# 24_LMS2_RX2_BB_ADC.net
KiCad netlist of a schematic drawn in Altium Designer
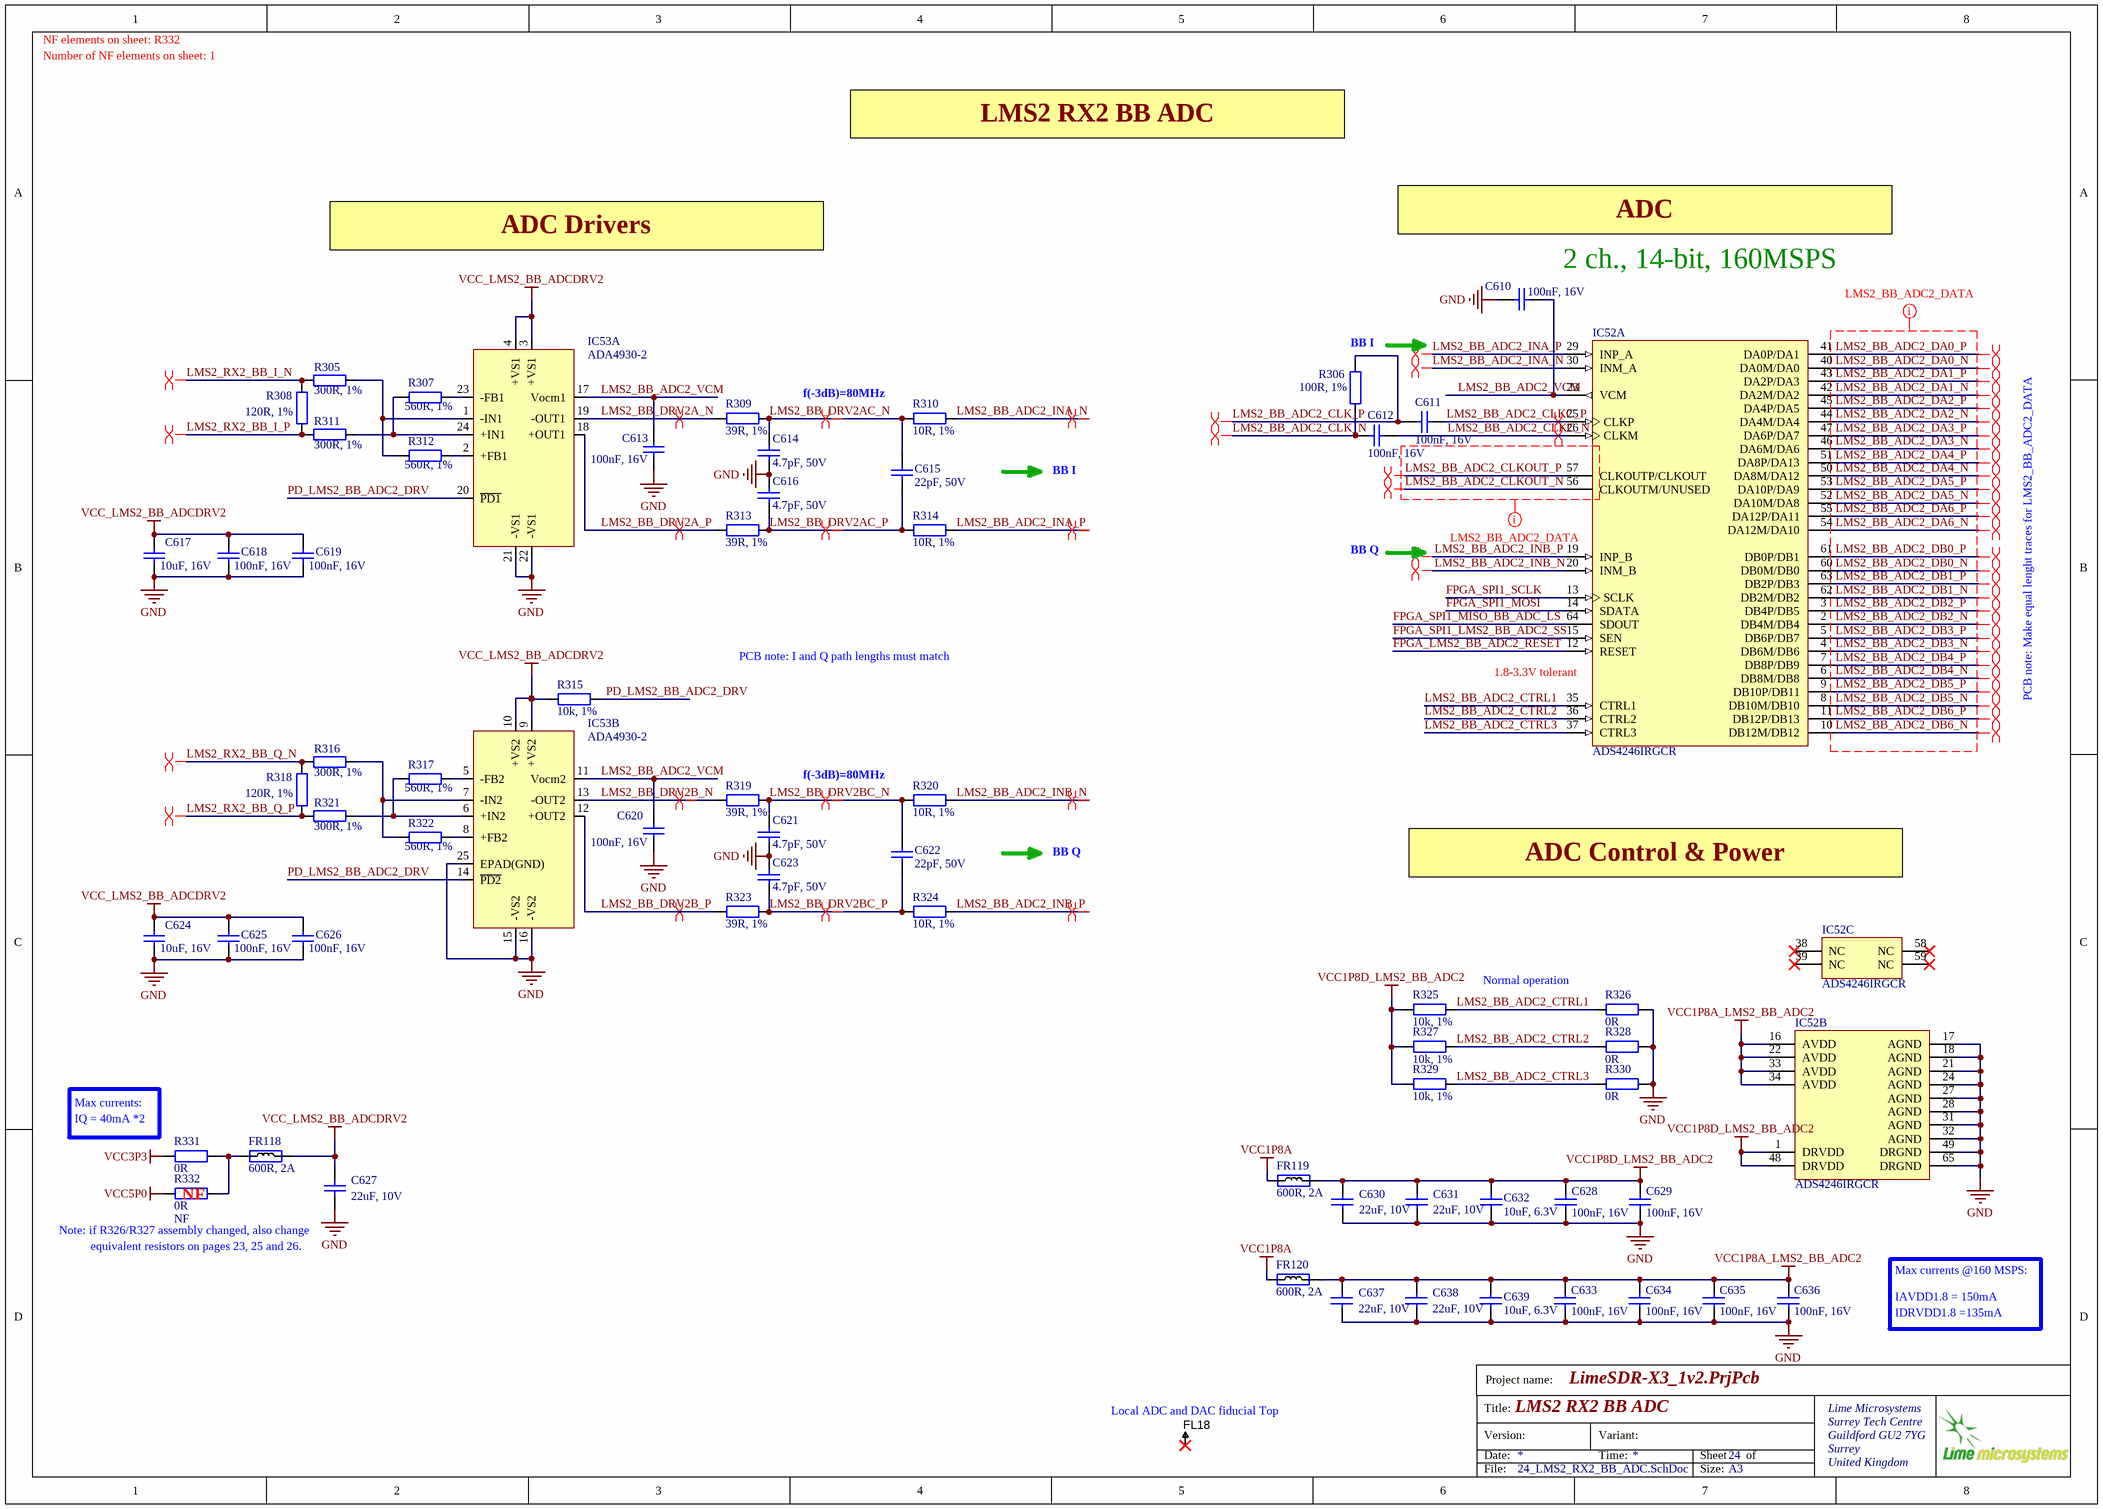
[diagram p0: 24_LMS2_RX2_BB_ADC.SchDoc]

(export (version "E")
  (design (tool "Eeschema 10.0.6"))
  (components
    (comp (ref "C610")
      (value "100nF, 16V")
      (footprint "CAP0402")
      (fields (field (name "TOLERANCE") "10 %") (field (name "MANUFACTURER") "Murata Electronics"))
      (libsource (lib "") (part "Cap_0603_6"))
    )
    (comp (ref "C611")
      (value "100nF, 16V")
      (footprint "CAP0402")
      (fields (field (name "TOLERANCE") "10 %") (field (name "MANUFACTURER") "Murata Electronics"))
      (libsource (lib "") (part "Cap_0603_6"))
    )
    (comp (ref "C612")
      (value "100nF, 16V")
      (footprint "CAP0402")
      (fields (field (name "TOLERANCE") "10 %") (field (name "MANUFACTURER") "Murata Electronics"))
      (libsource (lib "LimeFPGAboard_schLib") (part "Cap_0603"))
    )
    (comp (ref "C613")
      (value "100nF, 16V")
      (footprint "CAP0402")
      (fields (field (name "TOLERANCE") "10 %") (field (name "MANUFACTURER") "Murata Electronics"))
      (libsource (lib "LimeFPGAboard_schLib") (part "Cap_0603"))
    )
    (comp (ref "C614")
      (value "4.7pF, 50V")
      (footprint "CAP0402")
      (fields (field (name "MANUFACTURER") "MURATA"))
      (libsource (lib "") (part "Cap_0402_1"))
    )
    (comp (ref "C615")
      (value "22pF, 50V")
      (footprint "CAP0402")
      (fields (field (name "TOLERANCE") "±5%") (field (name "MANUFACTURER") "Yageo"))
      (libsource (lib "LimeMicroAltiumLib_schLib") (part "Cap_0402"))
    )
    (comp (ref "C616")
      (value "4.7pF, 50V")
      (footprint "CAP0402")
      (fields (field (name "MANUFACTURER") "MURATA"))
      (libsource (lib "") (part "Cap_0402_1"))
    )
    (comp (ref "C617")
      (value "10uF, 16V")
      (footprint "CAP0603")
      (fields (field (name "MANUFACTURER") "Yageo") (field (name "TOLERANCE") "±20%"))
      (libsource (lib "LimeMicroAltiumLib_schLib") (part "Cap_0603"))
    )
    (comp (ref "C618")
      (value "100nF, 16V")
      (footprint "CAP0402")
      (fields (field (name "TOLERANCE") "10 %") (field (name "MANUFACTURER") "Murata Electronics"))
      (libsource (lib "LimeFPGAboard_schLib") (part "Cap_0603"))
    )
    (comp (ref "C619")
      (value "100nF, 16V")
      (footprint "CAP0402")
      (fields (field (name "TOLERANCE") "10 %") (field (name "MANUFACTURER") "Murata Electronics"))
      (libsource (lib "LimeFPGAboard_schLib") (part "Cap_0603"))
    )
    (comp (ref "C620")
      (value "100nF, 16V")
      (footprint "CAP0402")
      (fields (field (name "TOLERANCE") "10 %") (field (name "MANUFACTURER") "Murata Electronics"))
      (libsource (lib "") (part "Cap_0603_5"))
    )
    (comp (ref "C621")
      (value "4.7pF, 50V")
      (footprint "CAP0402")
      (fields (field (name "MANUFACTURER") "MURATA"))
      (libsource (lib "") (part "Cap_0402_1"))
    )
    (comp (ref "C622")
      (value "22pF, 50V")
      (footprint "CAP0402")
      (fields (field (name "TOLERANCE") "±5%") (field (name "MANUFACTURER") "Yageo"))
      (libsource (lib "LimeMicroAltiumLib_schLib") (part "Cap_0402"))
    )
    (comp (ref "C623")
      (value "4.7pF, 50V")
      (footprint "CAP0402")
      (fields (field (name "MANUFACTURER") "MURATA"))
      (libsource (lib "") (part "Cap_0402_1"))
    )
    (comp (ref "C624")
      (value "10uF, 16V")
      (footprint "CAP0603")
      (fields (field (name "MANUFACTURER") "Yageo") (field (name "TOLERANCE") "±20%"))
      (libsource (lib "LimeMicroAltiumLib_schLib") (part "Cap_0603"))
    )
    (comp (ref "C625")
      (value "100nF, 16V")
      (footprint "CAP0402")
      (fields (field (name "TOLERANCE") "10 %") (field (name "MANUFACTURER") "Murata Electronics"))
      (libsource (lib "LimeFPGAboard_schLib") (part "Cap_0603"))
    )
    (comp (ref "C626")
      (value "100nF, 16V")
      (footprint "CAP0402")
      (fields (field (name "TOLERANCE") "10 %") (field (name "MANUFACTURER") "Murata Electronics"))
      (libsource (lib "LimeFPGAboard_schLib") (part "Cap_0603"))
    )
    (comp (ref "C627")
      (value "22uF, 10V")
      (footprint "CAP0603")
      (fields (field (name "TOLERANCE") "20 %") (field (name "MANUFACTURER") "TDK Corporation"))
      (libsource (lib "") (part "Cap_0603_7"))
    )
    (comp (ref "C628")
      (value "100nF, 16V")
      (footprint "CAP0402")
      (fields (field (name "TOLERANCE") "10 %") (field (name "MANUFACTURER") "Murata Electronics"))
      (libsource (lib "") (part "Cap_0603_3"))
    )
    (comp (ref "C629")
      (value "100nF, 16V")
      (footprint "CAP0402")
      (fields (field (name "TOLERANCE") "10 %") (field (name "MANUFACTURER") "Murata Electronics"))
      (libsource (lib "") (part "Cap_0603_3"))
    )
    (comp (ref "C630")
      (value "22uF, 10V")
      (footprint "CAP0603")
      (fields (field (name "TOLERANCE") "20 %") (field (name "MANUFACTURER") "TDK Corporation"))
      (libsource (lib "") (part "Cap_0603_3"))
    )
    (comp (ref "C631")
      (value "22uF, 10V")
      (footprint "CAP0603")
      (fields (field (name "TOLERANCE") "20 %") (field (name "MANUFACTURER") "TDK Corporation"))
      (libsource (lib "") (part "Cap_0603_3"))
    )
    (comp (ref "C632")
      (value "10uF, 6.3V")
      (footprint "CAP0603")
      (fields (field (name "TOLERANCE") "±20%") (field (name "MANUFACTURER") "Yageo"))
      (libsource (lib "") (part "Cap_0603_1"))
    )
    (comp (ref "C633")
      (value "100nF, 16V")
      (footprint "CAP0402")
      (fields (field (name "TOLERANCE") "10 %") (field (name "MANUFACTURER") "Murata Electronics"))
      (libsource (lib "") (part "Cap_0603_4"))
    )
    (comp (ref "C634")
      (value "100nF, 16V")
      (footprint "CAP0402")
      (fields (field (name "TOLERANCE") "10 %") (field (name "MANUFACTURER") "Murata Electronics"))
      (libsource (lib "") (part "Cap_0603_4"))
    )
    (comp (ref "C635")
      (value "100nF, 16V")
      (footprint "CAP0402")
      (fields (field (name "TOLERANCE") "10 %") (field (name "MANUFACTURER") "Murata Electronics"))
      (libsource (lib "") (part "Cap_0603_4"))
    )
    (comp (ref "C636")
      (value "100nF, 16V")
      (footprint "CAP0402")
      (fields (field (name "TOLERANCE") "10 %") (field (name "MANUFACTURER") "Murata Electronics"))
      (libsource (lib "") (part "Cap_0603_4"))
    )
    (comp (ref "C637")
      (value "22uF, 10V")
      (footprint "CAP0603")
      (fields (field (name "TOLERANCE") "20 %") (field (name "MANUFACTURER") "TDK Corporation"))
      (libsource (lib "") (part "Cap_0603_4"))
    )
    (comp (ref "C638")
      (value "22uF, 10V")
      (footprint "CAP0603")
      (fields (field (name "TOLERANCE") "20 %") (field (name "MANUFACTURER") "TDK Corporation"))
      (libsource (lib "") (part "Cap_0603_4"))
    )
    (comp (ref "C639")
      (value "10uF, 6.3V")
      (footprint "CAP0603")
      (fields (field (name "TOLERANCE") "±20%") (field (name "MANUFACTURER") "Yageo"))
      (libsource (lib "") (part "Cap_0603_2"))
    )
    (comp (ref "FL18")
      (value "Fiducial")
      (footprint "Fiducial_local")
      (libsource (lib "LimeMicroAltiumLib_schLib") (part "Fiducial"))
    )
    (comp (ref "FR118")
      (value "600R, 2A")
      (footprint "RES0805")
      (fields (field (name "MANUFACTURER") "TDK Corporation"))
      (libsource (lib "LimeMicroAltiumLib_schLib") (part "Ferrite"))
    )
    (comp (ref "FR119")
      (value "600R, 2A")
      (footprint "RES0805")
      (fields (field (name "MANUFACTURER") "TDK Corporation"))
      (libsource (lib "LimeFPGAboard_schLib") (part "Ferrite"))
    )
    (comp (ref "FR120")
      (value "600R, 2A")
      (footprint "RES0805")
      (fields (field (name "MANUFACTURER") "TDK Corporation"))
      (libsource (lib "LimeFPGAboard_schLib") (part "Ferrite"))
    )
    (comp (ref "IC52")
      (value "ADS4246IRGCR")
      (footprint "TI-RGC64-7400X7400TP_V")
      (description "14-Bit 160 MSPS Dual Low Power ADC, -40 to 85 degC, 64-pin QFN (RGC64), Green (RoHS & no Sb/Br)")
      (fields (field (name "MANUFACTURER") "Texas Instruments"))
      (libsource (lib "") (part "ADS4246IRGCR_1"))
    )
    (comp (ref "IC53")
      (value "ADA4930-2")
      (footprint "ADA4930-2_LFCSP-24")
      (fields (field (name "MANUFACTURER") "Analog Devices Inc."))
      (libsource (lib "LimeMicroAltiumLib_schLib") (part "ADA4930-2"))
    )
    (comp (ref "R305")
      (value "300R, 1%")
      (footprint "RES0402")
      (fields (field (name "TOLERANCE") "±1%") (field (name "MANUFACTURER") "Vishay Dale"))
      (libsource (lib "LimeFPGAboard_schLib") (part "Res_0402"))
    )
    (comp (ref "R306")
      (value "100R, 1%")
      (footprint "RES0402")
      (fields (field (name "TOLERANCE") "±1%") (field (name "MANUFACTURER") "Stackpole Electronics Inc."))
      (libsource (lib "LimeFPGAboard_schLib") (part "Res_0402"))
    )
    (comp (ref "R307")
      (value "560R, 1%")
      (footprint "RES0402")
      (fields (field (name "TOLERANCE") "±1%") (field (name "MANUFACTURER") "Vishay Dale"))
      (libsource (lib "LimeFPGAboard_schLib") (part "Res_0402"))
    )
    (comp (ref "R308")
      (value "120R, 1%")
      (footprint "RES0402")
      (fields (field (name "MANUFACTURER") "Yageo") (field (name "TOLERANCE") "1%"))
      (libsource (lib "") (part "Res_0402_1"))
    )
    (comp (ref "R309")
      (value "39R, 1%")
      (footprint "RES0402")
      (fields (field (name "MANUFACTURER") "Yageo") (field (name "TOLERANCE") "1%"))
      (libsource (lib "LimeMicroAltiumLib_schLib") (part "Res_0402"))
    )
    (comp (ref "R310")
      (value "10R, 1%")
      (footprint "RES0402")
      (fields (field (name "TOLERANCE") "1%"))
      (libsource (lib "LimeMicroAltiumLib_schLib") (part "Res_0402"))
    )
    (comp (ref "R311")
      (value "300R, 1%")
      (footprint "RES0402")
      (fields (field (name "TOLERANCE") "±1%") (field (name "MANUFACTURER") "Vishay Dale"))
      (libsource (lib "LimeFPGAboard_schLib") (part "Res_0402"))
    )
    (comp (ref "R312")
      (value "560R, 1%")
      (footprint "RES0402")
      (fields (field (name "TOLERANCE") "±1%") (field (name "MANUFACTURER") "Vishay Dale"))
      (libsource (lib "LimeFPGAboard_schLib") (part "Res_0402"))
    )
    (comp (ref "R313")
      (value "39R, 1%")
      (footprint "RES0402")
      (fields (field (name "MANUFACTURER") "Yageo") (field (name "TOLERANCE") "1%"))
      (libsource (lib "LimeMicroAltiumLib_schLib") (part "Res_0402"))
    )
    (comp (ref "R314")
      (value "10R, 1%")
      (footprint "RES0402")
      (fields (field (name "TOLERANCE") "1%"))
      (libsource (lib "LimeMicroAltiumLib_schLib") (part "Res_0402"))
    )
    (comp (ref "R315")
      (value "10k, 1%")
      (footprint "RES0402")
      (fields (field (name "MANUFACTURER") "Yageo") (field (name "TOLERANCE") "±1%"))
      (libsource (lib "LimeMicroAltiumLib_schLib") (part "Res_0402"))
    )
    (comp (ref "R316")
      (value "300R, 1%")
      (footprint "RES0402")
      (fields (field (name "TOLERANCE") "±1%") (field (name "MANUFACTURER") "Vishay Dale"))
      (libsource (lib "LimeFPGAboard_schLib") (part "Res_0402"))
    )
    (comp (ref "R317")
      (value "560R, 1%")
      (footprint "RES0402")
      (fields (field (name "TOLERANCE") "±1%") (field (name "MANUFACTURER") "Vishay Dale"))
      (libsource (lib "LimeFPGAboard_schLib") (part "Res_0402"))
    )
    (comp (ref "R318")
      (value "120R, 1%")
      (footprint "RES0402")
      (fields (field (name "MANUFACTURER") "Yageo") (field (name "TOLERANCE") "1%"))
      (libsource (lib "") (part "Res_0402_1"))
    )
    (comp (ref "R319")
      (value "39R, 1%")
      (footprint "RES0402")
      (fields (field (name "MANUFACTURER") "Yageo") (field (name "TOLERANCE") "1%"))
      (libsource (lib "LimeMicroAltiumLib_schLib") (part "Res_0402"))
    )
    (comp (ref "R320")
      (value "10R, 1%")
      (footprint "RES0402")
      (fields (field (name "TOLERANCE") "1%"))
      (libsource (lib "LimeMicroAltiumLib_schLib") (part "Res_0402"))
    )
    (comp (ref "R321")
      (value "300R, 1%")
      (footprint "RES0402")
      (fields (field (name "TOLERANCE") "±1%") (field (name "MANUFACTURER") "Vishay Dale"))
      (libsource (lib "LimeFPGAboard_schLib") (part "Res_0402"))
    )
    (comp (ref "R322")
      (value "560R, 1%")
      (footprint "RES0402")
      (fields (field (name "TOLERANCE") "±1%") (field (name "MANUFACTURER") "Vishay Dale"))
      (libsource (lib "LimeFPGAboard_schLib") (part "Res_0402"))
    )
    (comp (ref "R323")
      (value "39R, 1%")
      (footprint "RES0402")
      (fields (field (name "MANUFACTURER") "Yageo") (field (name "TOLERANCE") "1%"))
      (libsource (lib "LimeMicroAltiumLib_schLib") (part "Res_0402"))
    )
    (comp (ref "R324")
      (value "10R, 1%")
      (footprint "RES0402")
      (fields (field (name "TOLERANCE") "1%"))
      (libsource (lib "LimeMicroAltiumLib_schLib") (part "Res_0402"))
    )
    (comp (ref "R325")
      (value "10k, 1%")
      (footprint "RES0402")
      (fields (field (name "MANUFACTURER") "Yageo") (field (name "TOLERANCE") "±1%"))
      (libsource (lib "LimeMicroAltiumLib_schLib") (part "Res_0402"))
    )
    (comp (ref "R326")
      (value "0R")
      (footprint "RES0402")
      (fields (field (name "MANUFACTURER") "Yageo"))
      (libsource (lib "LimeFPGAboard_schLib") (part "Res_0402"))
    )
    (comp (ref "R327")
      (value "10k, 1%")
      (footprint "RES0402")
      (fields (field (name "MANUFACTURER") "Yageo") (field (name "TOLERANCE") "±1%"))
      (libsource (lib "LimeMicroAltiumLib_schLib") (part "Res_0402"))
    )
    (comp (ref "R328")
      (value "0R")
      (footprint "RES0402")
      (fields (field (name "MANUFACTURER") "Yageo"))
      (libsource (lib "LimeFPGAboard_schLib") (part "Res_0402"))
    )
    (comp (ref "R329")
      (value "10k, 1%")
      (footprint "RES0402")
      (fields (field (name "MANUFACTURER") "Yageo") (field (name "TOLERANCE") "±1%"))
      (libsource (lib "LimeMicroAltiumLib_schLib") (part "Res_0402"))
    )
    (comp (ref "R330")
      (value "0R")
      (footprint "RES0402")
      (fields (field (name "MANUFACTURER") "Yageo"))
      (libsource (lib "LimeFPGAboard_schLib") (part "Res_0402"))
    )
    (comp (ref "R331")
      (value "0R")
      (footprint "RES0402")
      (fields (field (name "MANUFACTURER") "Yageo") (field (name "TOLERANCE") "Jumper"))
      (libsource (lib "LimeMicroAltiumLib_schLib") (part "Res_0402"))
    )
    (comp (ref "R332")
      (value "0R")
      (footprint "RES0402")
      (fields
        (field (name "ASSEMBLY INFO") "NF")
        (field (name "MANUFACTURER") "Yageo")
        (field (name "TOLERANCE") "Jumper")
      )
      (libsource (lib "LimeMicroAltiumLib_schLib") (part "Res_0402"))
    )
  )
  (nets
    (net (code "1") (name "/FPGA_LMS2_BB_ADC2_RESET") (class "Default")
      (node (ref "IC52") (pin "12") (pinfunction "RESET_12") (pintype "input"))
    )
    (net (code "2") (name "/FPGA_SPI1_LMS2_BB_ADC2_SS") (class "Default")
      (node (ref "IC52") (pin "15") (pinfunction "SEN_15") (pintype "input"))
    )
    (net (code "3") (name "/FPGA_SPI1_MISO_BB_ADC_LS") (class "Default")
      (node (ref "IC52") (pin "64") (pinfunction "SDOUT_64") (pintype "tri_state"))
    )
    (net (code "4") (name "/FPGA_SPI1_MOSI") (class "Default")
      (node (ref "IC52") (pin "14") (pinfunction "SDATA_14") (pintype "input"))
    )
    (net (code "5") (name "/FPGA_SPI1_SCLK") (class "Default")
      (node (ref "IC52") (pin "13") (pinfunction "SCLK_13") (pintype "input"))
    )
    (net (code "6") (name "/LMS2_BB_ADC2_CLKC_N") (class "Default")
      (node (ref "C612") (pin "1") (pinfunction "1_1") (pintype "passive"))
      (node (ref "IC52") (pin "26") (pinfunction "CLKM_26") (pintype "input"))
    )
    (net (code "7") (name "/LMS2_BB_ADC2_CLKC_P") (class "Default")
      (node (ref "C611") (pin "1") (pinfunction "1_1") (pintype "passive"))
      (node (ref "IC52") (pin "25") (pinfunction "CLKP_25") (pintype "input"))
    )
    (net (code "8") (name "/LMS2_BB_ADC2_CLKOUT_N") (class "Default")
      (node (ref "IC52") (pin "56") (pinfunction "CLKOUTM/UNUSED_56") (pintype "tri_state"))
    )
    (net (code "9") (name "/LMS2_BB_ADC2_CLKOUT_P") (class "Default")
      (node (ref "IC52") (pin "57") (pinfunction "CLKOUTP/CLKOUT_57") (pintype "tri_state"))
    )
    (net (code "10") (name "/LMS2_BB_ADC2_CLK_N") (class "Default")
      (node (ref "C612") (pin "2") (pinfunction "2_2") (pintype "passive"))
      (node (ref "R306") (pin "1") (pinfunction "1_1") (pintype "passive"))
    )
    (net (code "11") (name "/LMS2_BB_ADC2_CLK_P") (class "Default")
      (node (ref "C611") (pin "2") (pinfunction "2_2") (pintype "passive"))
      (node (ref "R306") (pin "2") (pinfunction "2_2") (pintype "passive"))
    )
    (net (code "12") (name "/LMS2_BB_ADC2_CTRL1") (class "Default")
      (node (ref "IC52") (pin "35") (pinfunction "CTRL1_35") (pintype "input"))
      (node (ref "R325") (pin "1") (pinfunction "1_1") (pintype "passive"))
      (node (ref "R326") (pin "2") (pinfunction "2_2") (pintype "passive"))
    )
    (net (code "13") (name "/LMS2_BB_ADC2_CTRL2") (class "Default")
      (node (ref "IC52") (pin "36") (pinfunction "CTRL2_36") (pintype "input"))
      (node (ref "R327") (pin "1") (pinfunction "1_1") (pintype "passive"))
      (node (ref "R328") (pin "2") (pinfunction "2_2") (pintype "passive"))
    )
    (net (code "14") (name "/LMS2_BB_ADC2_CTRL3") (class "Default")
      (node (ref "IC52") (pin "37") (pinfunction "CTRL3_37") (pintype "input"))
      (node (ref "R329") (pin "1") (pinfunction "1_1") (pintype "passive"))
      (node (ref "R330") (pin "2") (pinfunction "2_2") (pintype "passive"))
    )
    (net (code "15") (name "/LMS2_BB_ADC2_DA0_N") (class "Default")
      (node (ref "IC52") (pin "40") (pinfunction "DA0M/DA0_40") (pintype "tri_state"))
    )
    (net (code "16") (name "/LMS2_BB_ADC2_DA0_P") (class "Default")
      (node (ref "IC52") (pin "41") (pinfunction "DA0P/DA1_41") (pintype "tri_state"))
    )
    (net (code "17") (name "/LMS2_BB_ADC2_DA1_N") (class "Default")
      (node (ref "IC52") (pin "42") (pinfunction "DA2M/DA2_42") (pintype "tri_state"))
    )
    (net (code "18") (name "/LMS2_BB_ADC2_DA1_P") (class "Default")
      (node (ref "IC52") (pin "43") (pinfunction "DA2P/DA3_43") (pintype "tri_state"))
    )
    (net (code "19") (name "/LMS2_BB_ADC2_DA2_N") (class "Default")
      (node (ref "IC52") (pin "44") (pinfunction "DA4M/DA4_44") (pintype "tri_state"))
    )
    (net (code "20") (name "/LMS2_BB_ADC2_DA2_P") (class "Default")
      (node (ref "IC52") (pin "45") (pinfunction "DA4P/DA5_45") (pintype "tri_state"))
    )
    (net (code "21") (name "/LMS2_BB_ADC2_DA3_N") (class "Default")
      (node (ref "IC52") (pin "46") (pinfunction "DA6M/DA6_46") (pintype "tri_state"))
    )
    (net (code "22") (name "/LMS2_BB_ADC2_DA3_P") (class "Default")
      (node (ref "IC52") (pin "47") (pinfunction "DA6P/DA7_47") (pintype "tri_state"))
    )
    (net (code "23") (name "/LMS2_BB_ADC2_DA4_N") (class "Default")
      (node (ref "IC52") (pin "50") (pinfunction "DA8M/DA12_50") (pintype "tri_state"))
    )
    (net (code "24") (name "/LMS2_BB_ADC2_DA4_P") (class "Default")
      (node (ref "IC52") (pin "51") (pinfunction "DA8P/DA13_51") (pintype "tri_state"))
    )
    (net (code "25") (name "/LMS2_BB_ADC2_DA5_N") (class "Default")
      (node (ref "IC52") (pin "52") (pinfunction "DA10M/DA8_52") (pintype "tri_state"))
    )
    (net (code "26") (name "/LMS2_BB_ADC2_DA5_P") (class "Default")
      (node (ref "IC52") (pin "53") (pinfunction "DA10P/DA9_53") (pintype "tri_state"))
    )
    (net (code "27") (name "/LMS2_BB_ADC2_DA6_N") (class "Default")
      (node (ref "IC52") (pin "54") (pinfunction "DA12M/DA10_54") (pintype "tri_state"))
    )
    (net (code "28") (name "/LMS2_BB_ADC2_DA6_P") (class "Default")
      (node (ref "IC52") (pin "55") (pinfunction "DA12P/DA11_55") (pintype "tri_state"))
    )
    (net (code "29") (name "/LMS2_BB_ADC2_DB0_N") (class "Default")
      (node (ref "IC52") (pin "60") (pinfunction "DB0M/DB0_60") (pintype "tri_state"))
    )
    (net (code "30") (name "/LMS2_BB_ADC2_DB0_P") (class "Default")
      (node (ref "IC52") (pin "61") (pinfunction "DB0P/DB1_61") (pintype "tri_state"))
    )
    (net (code "31") (name "/LMS2_BB_ADC2_DB1_N") (class "Default")
      (node (ref "IC52") (pin "62") (pinfunction "DB2M/DB2_62") (pintype "tri_state"))
    )
    (net (code "32") (name "/LMS2_BB_ADC2_DB1_P") (class "Default")
      (node (ref "IC52") (pin "63") (pinfunction "DB2P/DB3_63") (pintype "tri_state"))
    )
    (net (code "33") (name "/LMS2_BB_ADC2_DB2_N") (class "Default")
      (node (ref "IC52") (pin "2") (pinfunction "DB4M/DB4_2") (pintype "tri_state"))
    )
    (net (code "34") (name "/LMS2_BB_ADC2_DB2_P") (class "Default")
      (node (ref "IC52") (pin "3") (pinfunction "DB4P/DB5_3") (pintype "tri_state"))
    )
    (net (code "35") (name "/LMS2_BB_ADC2_DB3_N") (class "Default")
      (node (ref "IC52") (pin "4") (pinfunction "DB6M/DB6_4") (pintype "tri_state"))
    )
    (net (code "36") (name "/LMS2_BB_ADC2_DB3_P") (class "Default")
      (node (ref "IC52") (pin "5") (pinfunction "DB6P/DB7_5") (pintype "tri_state"))
    )
    (net (code "37") (name "/LMS2_BB_ADC2_DB4_N") (class "Default")
      (node (ref "IC52") (pin "6") (pinfunction "DB8M/DB8_6") (pintype "tri_state"))
    )
    (net (code "38") (name "/LMS2_BB_ADC2_DB4_P") (class "Default")
      (node (ref "IC52") (pin "7") (pinfunction "DB8P/DB9_7") (pintype "tri_state"))
    )
    (net (code "39") (name "/LMS2_BB_ADC2_DB5_N") (class "Default")
      (node (ref "IC52") (pin "8") (pinfunction "DB10M/DB10_8") (pintype "tri_state"))
    )
    (net (code "40") (name "/LMS2_BB_ADC2_DB5_P") (class "Default")
      (node (ref "IC52") (pin "9") (pinfunction "DB10P/DB11_9") (pintype "tri_state"))
    )
    (net (code "41") (name "/LMS2_BB_ADC2_DB6_N") (class "Default")
      (node (ref "IC52") (pin "10") (pinfunction "DB12M/DB12_10") (pintype "tri_state"))
    )
    (net (code "42") (name "/LMS2_BB_ADC2_DB6_P") (class "Default")
      (node (ref "IC52") (pin "11") (pinfunction "DB12P/DB13_11") (pintype "tri_state"))
    )
    (net (code "43") (name "/LMS2_BB_ADC2_INA_N") (class "Default")
      (node (ref "IC52") (pin "30") (pinfunction "INM_A_30") (pintype "input"))
      (node (ref "R310") (pin "1") (pinfunction "1_1") (pintype "passive"))
    )
    (net (code "44") (name "/LMS2_BB_ADC2_INA_P") (class "Default")
      (node (ref "IC52") (pin "29") (pinfunction "INP_A_29") (pintype "input"))
      (node (ref "R314") (pin "1") (pinfunction "1_1") (pintype "passive"))
    )
    (net (code "45") (name "/LMS2_BB_ADC2_INB_N") (class "Default")
      (node (ref "IC52") (pin "20") (pinfunction "INM_B_20") (pintype "input"))
      (node (ref "R320") (pin "1") (pinfunction "1_1") (pintype "passive"))
    )
    (net (code "46") (name "/LMS2_BB_ADC2_INB_P") (class "Default")
      (node (ref "IC52") (pin "19") (pinfunction "INP_B_19") (pintype "input"))
      (node (ref "R324") (pin "1") (pinfunction "1_1") (pintype "passive"))
    )
    (net (code "47") (name "/LMS2_BB_ADC2_VCM") (class "Default")
      (node (ref "C610") (pin "2") (pinfunction "2_2") (pintype "passive"))
      (node (ref "C613") (pin "1") (pinfunction "1_1") (pintype "passive"))
      (node (ref "C620") (pin "1") (pinfunction "1_1") (pintype "passive"))
      (node (ref "IC52") (pin "23") (pinfunction "VCM_23") (pintype "output"))
      (node (ref "IC53") (pin "11") (pinfunction "Vocm2_11") (pintype "input"))
      (node (ref "IC53") (pin "17") (pinfunction "Vocm1_17") (pintype "input"))
    )
    (net (code "48") (name "/LMS2_BB_DRV2AC_N") (class "Default")
      (node (ref "C614") (pin "1") (pinfunction "1_1") (pintype "passive"))
      (node (ref "C615") (pin "1") (pinfunction "1_1") (pintype "passive"))
      (node (ref "R309") (pin "1") (pinfunction "1_1") (pintype "passive"))
      (node (ref "R310") (pin "2") (pinfunction "2_2") (pintype "passive"))
    )
    (net (code "49") (name "/LMS2_BB_DRV2AC_P") (class "Default")
      (node (ref "C615") (pin "2") (pinfunction "2_2") (pintype "passive"))
      (node (ref "C616") (pin "2") (pinfunction "2_2") (pintype "passive"))
      (node (ref "R313") (pin "1") (pinfunction "1_1") (pintype "passive"))
      (node (ref "R314") (pin "2") (pinfunction "2_2") (pintype "passive"))
    )
    (net (code "50") (name "/LMS2_BB_DRV2A_N") (class "Default")
      (node (ref "IC53") (pin "19") (pinfunction "-OUT1_19") (pintype "output"))
      (node (ref "R309") (pin "2") (pinfunction "2_2") (pintype "passive"))
    )
    (net (code "51") (name "/LMS2_BB_DRV2A_P") (class "Default")
      (node (ref "IC53") (pin "18") (pinfunction "+OUT1_18") (pintype "output"))
      (node (ref "R313") (pin "2") (pinfunction "2_2") (pintype "passive"))
    )
    (net (code "52") (name "/LMS2_BB_DRV2BC_N") (class "Default")
      (node (ref "C621") (pin "1") (pinfunction "1_1") (pintype "passive"))
      (node (ref "C622") (pin "1") (pinfunction "1_1") (pintype "passive"))
      (node (ref "R319") (pin "1") (pinfunction "1_1") (pintype "passive"))
      (node (ref "R320") (pin "2") (pinfunction "2_2") (pintype "passive"))
    )
    (net (code "53") (name "/LMS2_BB_DRV2BC_P") (class "Default")
      (node (ref "C622") (pin "2") (pinfunction "2_2") (pintype "passive"))
      (node (ref "C623") (pin "2") (pinfunction "2_2") (pintype "passive"))
      (node (ref "R323") (pin "1") (pinfunction "1_1") (pintype "passive"))
      (node (ref "R324") (pin "2") (pinfunction "2_2") (pintype "passive"))
    )
    (net (code "54") (name "/LMS2_BB_DRV2B_N") (class "Default")
      (node (ref "IC53") (pin "13") (pinfunction "-OUT2_13") (pintype "output"))
      (node (ref "R319") (pin "2") (pinfunction "2_2") (pintype "passive"))
    )
    (net (code "55") (name "/LMS2_BB_DRV2B_P") (class "Default")
      (node (ref "IC53") (pin "12") (pinfunction "+OUT2_12") (pintype "output"))
      (node (ref "R323") (pin "2") (pinfunction "2_2") (pintype "passive"))
    )
    (net (code "56") (name "/LMS2_RX2_BB_I_N") (class "Default")
      (node (ref "R305") (pin "2") (pinfunction "2_2") (pintype "passive"))
      (node (ref "R308") (pin "2") (pinfunction "2_2") (pintype "passive"))
    )
    (net (code "57") (name "/LMS2_RX2_BB_I_P") (class "Default")
      (node (ref "R308") (pin "1") (pinfunction "1_1") (pintype "passive"))
      (node (ref "R311") (pin "2") (pinfunction "2_2") (pintype "passive"))
    )
    (net (code "58") (name "/LMS2_RX2_BB_Q_N") (class "Default")
      (node (ref "R316") (pin "2") (pinfunction "2_2") (pintype "passive"))
      (node (ref "R318") (pin "2") (pinfunction "2_2") (pintype "passive"))
    )
    (net (code "59") (name "/LMS2_RX2_BB_Q_P") (class "Default")
      (node (ref "R318") (pin "1") (pinfunction "1_1") (pintype "passive"))
      (node (ref "R321") (pin "2") (pinfunction "2_2") (pintype "passive"))
    )
    (net (code "60") (name "/PD_LMS2_BB_ADC2_DRV") (class "Default")
      (node (ref "IC53") (pin "14") (pinfunction "~{PD2}_14") (pintype "input"))
      (node (ref "IC53") (pin "20") (pinfunction "~{PD1}_20") (pintype "input"))
      (node (ref "R315") (pin "1") (pinfunction "1_1") (pintype "passive"))
    )
    (net (code "61") (name "GND") (class "Default")
      (node (ref "C610") (pin "1") (pinfunction "1_1") (pintype "passive"))
      (node (ref "C613") (pin "2") (pinfunction "2_2") (pintype "passive"))
      (node (ref "C614") (pin "2") (pinfunction "2_2") (pintype "passive"))
      (node (ref "C616") (pin "1") (pinfunction "1_1") (pintype "passive"))
      (node (ref "C617") (pin "1") (pinfunction "1_1") (pintype "passive"))
      (node (ref "C618") (pin "2") (pinfunction "2_2") (pintype "passive"))
      (node (ref "C619") (pin "2") (pinfunction "2_2") (pintype "passive"))
      (node (ref "C620") (pin "2") (pinfunction "2_2") (pintype "passive"))
      (node (ref "C621") (pin "2") (pinfunction "2_2") (pintype "passive"))
      (node (ref "C623") (pin "1") (pinfunction "1_1") (pintype "passive"))
      (node (ref "C624") (pin "1") (pinfunction "1_1") (pintype "passive"))
      (node (ref "C625") (pin "2") (pinfunction "2_2") (pintype "passive"))
      (node (ref "C626") (pin "2") (pinfunction "2_2") (pintype "passive"))
      (node (ref "C627") (pin "1") (pinfunction "1_1") (pintype "passive"))
      (node (ref "C628") (pin "1") (pinfunction "1_1") (pintype "passive"))
      (node (ref "C629") (pin "1") (pinfunction "1_1") (pintype "passive"))
      (node (ref "C630") (pin "1") (pinfunction "1_1") (pintype "passive"))
      (node (ref "C631") (pin "1") (pinfunction "1_1") (pintype "passive"))
      (node (ref "C632") (pin "2") (pinfunction "2_2") (pintype "passive"))
      (node (ref "C633") (pin "1") (pinfunction "1_1") (pintype "passive"))
      (node (ref "C634") (pin "1") (pinfunction "1_1") (pintype "passive"))
      (node (ref "C635") (pin "1") (pinfunction "1_1") (pintype "passive"))
      (node (ref "C636") (pin "1") (pinfunction "1_1") (pintype "passive"))
      (node (ref "C637") (pin "1") (pinfunction "1_1") (pintype "passive"))
      (node (ref "C638") (pin "1") (pinfunction "1_1") (pintype "passive"))
      (node (ref "C639") (pin "2") (pinfunction "2_2") (pintype "passive"))
      (node (ref "IC52") (pin "17") (pinfunction "AGND_17") (pintype "power_in"))
      (node (ref "IC52") (pin "18") (pinfunction "AGND_18") (pintype "power_in"))
      (node (ref "IC52") (pin "21") (pinfunction "AGND_21") (pintype "power_in"))
      (node (ref "IC52") (pin "24") (pinfunction "AGND_24") (pintype "power_in"))
      (node (ref "IC52") (pin "27") (pinfunction "AGND_27") (pintype "power_in"))
      (node (ref "IC52") (pin "28") (pinfunction "AGND_28") (pintype "power_in"))
      (node (ref "IC52") (pin "31") (pinfunction "AGND_31") (pintype "power_in"))
      (node (ref "IC52") (pin "32") (pinfunction "AGND_32") (pintype "power_in"))
      (node (ref "IC52") (pin "49") (pinfunction "DRGND_49") (pintype "power_in"))
      (node (ref "IC52") (pin "65") (pinfunction "DRGND_65") (pintype "power_in"))
      (node (ref "IC53") (pin "15") (pinfunction "-VS2_15") (pintype "power_in"))
      (node (ref "IC53") (pin "16") (pinfunction "-VS2_16") (pintype "power_in"))
      (node (ref "IC53") (pin "21") (pinfunction "-VS1_21") (pintype "power_in"))
      (node (ref "IC53") (pin "22") (pinfunction "-VS1_22") (pintype "power_in"))
      (node (ref "IC53") (pin "25") (pinfunction "EPAD(GND)_25") (pintype "passive"))
      (node (ref "R326") (pin "1") (pinfunction "1_1") (pintype "passive"))
      (node (ref "R328") (pin "1") (pinfunction "1_1") (pintype "passive"))
      (node (ref "R330") (pin "1") (pinfunction "1_1") (pintype "passive"))
    )
    (net (code "62") (name "Net-(FR118-Pad1)") (class "Default")
      (node (ref "FR118") (pin "1") (pinfunction "1_1") (pintype "passive"))
      (node (ref "R331") (pin "1") (pinfunction "1_1") (pintype "passive"))
      (node (ref "R332") (pin "1") (pinfunction "1_1") (pintype "passive"))
    )
    (net (code "63") (name "Net-(IC53A-+FB1)") (class "Default")
      (node (ref "IC53") (pin "2") (pinfunction "+FB1_2") (pintype "output"))
      (node (ref "R312") (pin "1") (pinfunction "1_1") (pintype "passive"))
    )
    (net (code "64") (name "Net-(IC53A-+IN1)") (class "Default")
      (node (ref "IC53") (pin "24") (pinfunction "+IN1_24") (pintype "input"))
      (node (ref "R307") (pin "2") (pinfunction "2_2") (pintype "passive"))
      (node (ref "R311") (pin "1") (pinfunction "1_1") (pintype "passive"))
    )
    (net (code "65") (name "Net-(IC53A--FB1)") (class "Default")
      (node (ref "IC53") (pin "23") (pinfunction "-FB1_23") (pintype "output"))
      (node (ref "R307") (pin "1") (pinfunction "1_1") (pintype "passive"))
    )
    (net (code "66") (name "Net-(IC53A--IN1)") (class "Default")
      (node (ref "IC53") (pin "1") (pinfunction "-IN1_1") (pintype "input"))
      (node (ref "R305") (pin "1") (pinfunction "1_1") (pintype "passive"))
      (node (ref "R312") (pin "2") (pinfunction "2_2") (pintype "passive"))
    )
    (net (code "67") (name "Net-(IC53B-+FB2)") (class "Default")
      (node (ref "IC53") (pin "8") (pinfunction "+FB2_8") (pintype "output"))
      (node (ref "R322") (pin "1") (pinfunction "1_1") (pintype "passive"))
    )
    (net (code "68") (name "Net-(IC53B-+IN2)") (class "Default")
      (node (ref "IC53") (pin "6") (pinfunction "+IN2_6") (pintype "input"))
      (node (ref "R317") (pin "2") (pinfunction "2_2") (pintype "passive"))
      (node (ref "R321") (pin "1") (pinfunction "1_1") (pintype "passive"))
    )
    (net (code "69") (name "Net-(IC53B--FB2)") (class "Default")
      (node (ref "IC53") (pin "5") (pinfunction "-FB2_5") (pintype "output"))
      (node (ref "R317") (pin "1") (pinfunction "1_1") (pintype "passive"))
    )
    (net (code "70") (name "Net-(IC53B--IN2)") (class "Default")
      (node (ref "IC53") (pin "7") (pinfunction "-IN2_7") (pintype "input"))
      (node (ref "R316") (pin "1") (pinfunction "1_1") (pintype "passive"))
      (node (ref "R322") (pin "2") (pinfunction "2_2") (pintype "passive"))
    )
    (net (code "71") (name "VCC1P8A") (class "Default")
      (node (ref "FR119") (pin "1") (pinfunction "1_1") (pintype "passive"))
      (node (ref "FR120") (pin "1") (pinfunction "1_1") (pintype "passive"))
    )
    (net (code "72") (name "VCC1P8A_LMS2_BB_ADC2") (class "Default")
      (node (ref "C633") (pin "2") (pinfunction "2_2") (pintype "passive"))
      (node (ref "C634") (pin "2") (pinfunction "2_2") (pintype "passive"))
      (node (ref "C635") (pin "2") (pinfunction "2_2") (pintype "passive"))
      (node (ref "C636") (pin "2") (pinfunction "2_2") (pintype "passive"))
      (node (ref "C637") (pin "2") (pinfunction "2_2") (pintype "passive"))
      (node (ref "C638") (pin "2") (pinfunction "2_2") (pintype "passive"))
      (node (ref "C639") (pin "1") (pinfunction "1_1") (pintype "passive"))
      (node (ref "FR120") (pin "2") (pinfunction "2_2") (pintype "passive"))
      (node (ref "IC52") (pin "16") (pinfunction "AVDD_16") (pintype "power_in"))
      (node (ref "IC52") (pin "22") (pinfunction "AVDD_22") (pintype "power_in"))
      (node (ref "IC52") (pin "33") (pinfunction "AVDD_33") (pintype "power_in"))
      (node (ref "IC52") (pin "34") (pinfunction "AVDD_34") (pintype "power_in"))
    )
    (net (code "73") (name "VCC1P8D_LMS2_BB_ADC2") (class "Default")
      (node (ref "C628") (pin "2") (pinfunction "2_2") (pintype "passive"))
      (node (ref "C629") (pin "2") (pinfunction "2_2") (pintype "passive"))
      (node (ref "C630") (pin "2") (pinfunction "2_2") (pintype "passive"))
      (node (ref "C631") (pin "2") (pinfunction "2_2") (pintype "passive"))
      (node (ref "C632") (pin "1") (pinfunction "1_1") (pintype "passive"))
      (node (ref "FR119") (pin "2") (pinfunction "2_2") (pintype "passive"))
      (node (ref "IC52") (pin "1") (pinfunction "DRVDD_1") (pintype "power_in"))
      (node (ref "IC52") (pin "48") (pinfunction "DRVDD_48") (pintype "power_in"))
      (node (ref "R325") (pin "2") (pinfunction "2_2") (pintype "passive"))
      (node (ref "R327") (pin "2") (pinfunction "2_2") (pintype "passive"))
      (node (ref "R329") (pin "2") (pinfunction "2_2") (pintype "passive"))
    )
    (net (code "74") (name "VCC3P3") (class "Default")
      (node (ref "R331") (pin "2") (pinfunction "2_2") (pintype "passive"))
    )
    (net (code "75") (name "VCC5P0") (class "Default")
      (node (ref "R332") (pin "2") (pinfunction "2_2") (pintype "passive"))
    )
    (net (code "76") (name "VCC_LMS2_BB_ADCDRV2") (class "Default")
      (node (ref "C617") (pin "2") (pinfunction "2_2") (pintype "passive"))
      (node (ref "C618") (pin "1") (pinfunction "1_1") (pintype "passive"))
      (node (ref "C619") (pin "1") (pinfunction "1_1") (pintype "passive"))
      (node (ref "C624") (pin "2") (pinfunction "2_2") (pintype "passive"))
      (node (ref "C625") (pin "1") (pinfunction "1_1") (pintype "passive"))
      (node (ref "C626") (pin "1") (pinfunction "1_1") (pintype "passive"))
      (node (ref "C627") (pin "2") (pinfunction "2_2") (pintype "passive"))
      (node (ref "FR118") (pin "2") (pinfunction "2_2") (pintype "passive"))
      (node (ref "IC53") (pin "10") (pinfunction "+VS2_10") (pintype "power_in"))
      (node (ref "IC53") (pin "3") (pinfunction "+VS1_3") (pintype "power_in"))
      (node (ref "IC53") (pin "4") (pinfunction "+VS1_4") (pintype "power_in"))
      (node (ref "IC53") (pin "9") (pinfunction "+VS2_9") (pintype "power_in"))
      (node (ref "R315") (pin "2") (pinfunction "2_2") (pintype "passive"))
    )
    (net (code "77") (name "unconnected-(FL18-Pad1)") (class "Default")
      (node (ref "FL18") (pin "1") (pintype "passive+no_connect"))
    )
    (net (code "78") (name "unconnected-(IC52C-NC-Pad38)") (class "Default")
      (node (ref "IC52") (pin "38") (pinfunction "NC_38") (pintype "passive+no_connect"))
    )
    (net (code "79") (name "unconnected-(IC52C-NC-Pad39)") (class "Default")
      (node (ref "IC52") (pin "39") (pinfunction "NC_39") (pintype "passive+no_connect"))
    )
    (net (code "80") (name "unconnected-(IC52C-NC-Pad58)") (class "Default")
      (node (ref "IC52") (pin "58") (pinfunction "NC_58") (pintype "passive+no_connect"))
    )
    (net (code "81") (name "unconnected-(IC52C-NC-Pad59)") (class "Default")
      (node (ref "IC52") (pin "59") (pinfunction "NC_59") (pintype "passive+no_connect"))
    )
  )
)
